# M1_75S2.net
KiCad netlist of a schematic drawn in Altium Designer
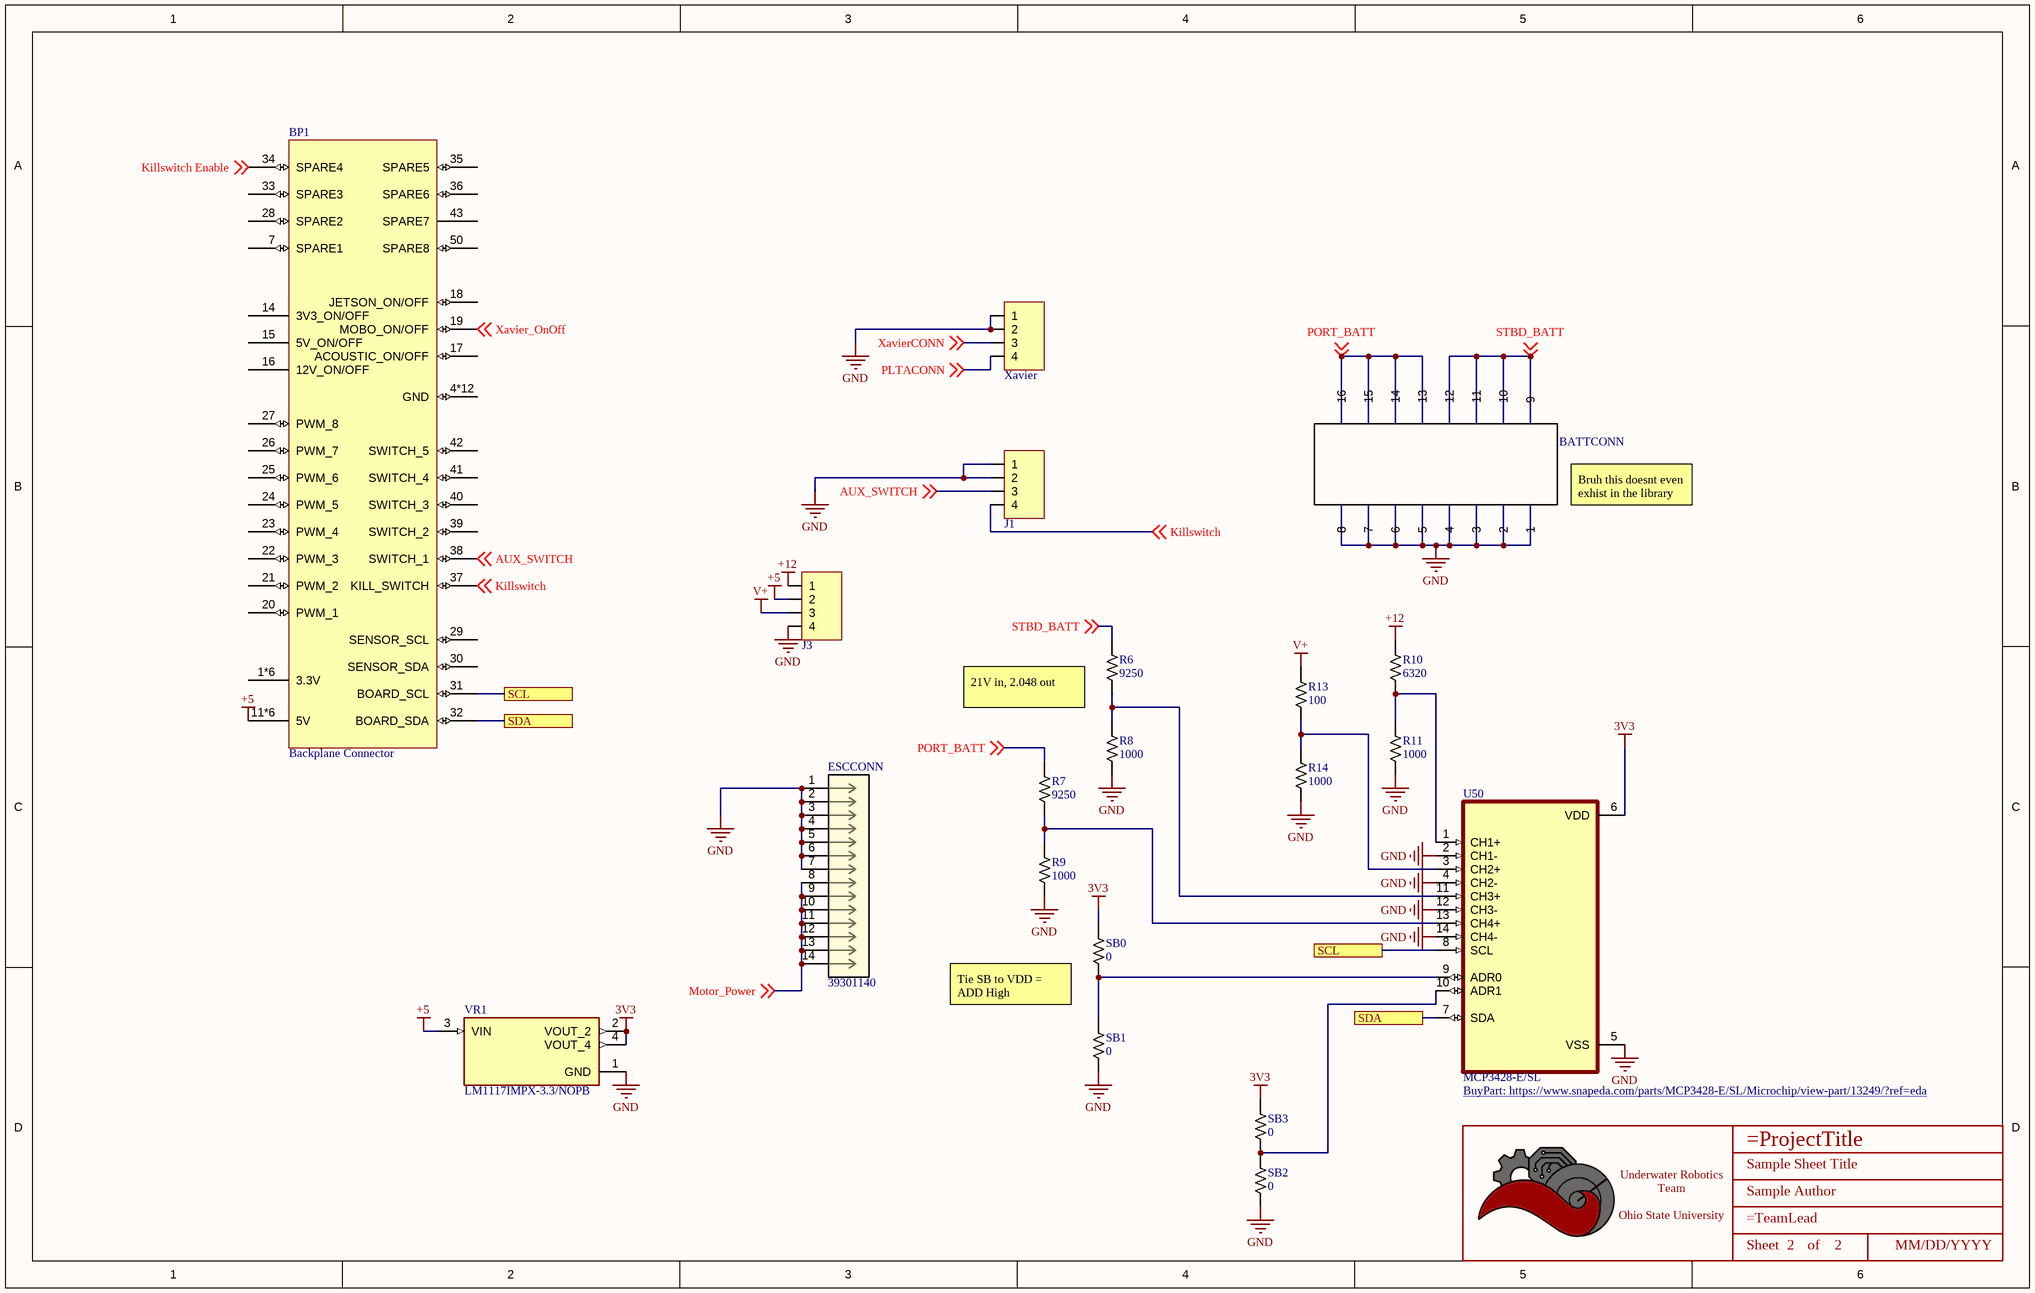
[diagram p0: M1_75S2.SchDoc]

(export (version "E")
  (design (tool "Eeschema 10.0.6"))
  (components
    (comp (ref "BATTCONN")
      (value "BatteryConnector")
      (footprint "CONN_MOLEX_MINIFIT JR_16 POS_R/A - duplicate")
      (libsource (lib "Connectors") (part "BatteryConnector"))
    )
    (comp (ref "BP1")
      (value "Backplane Connector")
      (footprint "BACKPLANE_EDGE_CONN")
      (description "Titan Backplane Edge Connector")
      (libsource (lib "Connectors") (part "BACKPLANE_EDGE_CONN"))
    )
    (comp (ref "ESCCONN")
      (value "39301140")
      (footprint "CON_39301140")
      (description "No Description Available")
      (fields (field (name "COPYRIGHT") "Copyright (C) 2022 Ultra Librarian. All rights reserved."))
      (libsource (lib "39301140") (part "39301140"))
    )
    (comp (ref "J1")
      (value "4 POS R/A")
      (footprint "CONN_MOLEX_MINIFIT JR_4 POS_R/A")
      (description "Molex Minifit Jr. 5569 \r\n4 Pos R/A Natural")
      (fields (field (name "MANUFACTURER") "Molex") (field (name "CREATED BY") "Flip B"))
      (libsource (lib "Connectors") (part "CONN_MOLEX_MINIFIT JR_4POS_R/A"))
    )
    (comp (ref "J3")
      (value "4 POS R/A")
      (footprint "CONN_MOLEX_MINIFIT JR_4 POS_R/A")
      (description "Molex Minifit Jr. 5569 \r\n4 Pos R/A Natural")
      (fields (field (name "MANUFACTURER") "Molex") (field (name "CREATED BY") "Flip B"))
      (libsource (lib "Connectors") (part "CONN_MOLEX_MINIFIT JR_4POS_R/A"))
    )
    (comp (ref "R6")
      (value "100 Ohm 5% 1/8W")
      (footprint "RESISTOR_0603")
      (description "RES 100 OHM 5% 1/8W 0603")
      (fields
        (field (name "TOLERANCE") "+/- 5%")
        (field (name "VALUE  (OHMS)") "9250")
        (field (name "MADE BY") "Flip B")
      )
      (libsource (lib "Resistors") (part "RESISTOR_100_0603"))
    )
    (comp (ref "R7")
      (value "100 Ohm 5% 1/8W")
      (footprint "RESISTOR_0603")
      (description "RES 100 OHM 5% 1/8W 0603")
      (fields
        (field (name "TOLERANCE") "+/- 5%")
        (field (name "VALUE  (OHMS)") "9250")
        (field (name "MADE BY") "Flip B")
      )
      (libsource (lib "Resistors") (part "RESISTOR_100_0603"))
    )
    (comp (ref "R8")
      (value "100 Ohm 5% 1/8W")
      (footprint "RESISTOR_0603")
      (description "RES 100 OHM 5% 1/8W 0603")
      (fields
        (field (name "TOLERANCE") "+/- 5%")
        (field (name "VALUE  (OHMS)") "1000")
        (field (name "MADE BY") "Flip B")
      )
      (libsource (lib "Resistors") (part "RESISTOR_100_0603"))
    )
    (comp (ref "R9")
      (value "100 Ohm 5% 1/8W")
      (footprint "RESISTOR_0603")
      (description "RES 100 OHM 5% 1/8W 0603")
      (fields
        (field (name "TOLERANCE") "+/- 5%")
        (field (name "VALUE  (OHMS)") "1000")
        (field (name "MADE BY") "Flip B")
      )
      (libsource (lib "Resistors") (part "RESISTOR_100_0603"))
    )
    (comp (ref "R10")
      (value "100 Ohm 5% 1/8W")
      (footprint "RESISTOR_0603")
      (description "RES 100 OHM 5% 1/8W 0603")
      (fields
        (field (name "TOLERANCE") "+/- 5%")
        (field (name "VALUE  (OHMS)") "6320")
        (field (name "MADE BY") "Flip B")
      )
      (libsource (lib "Resistors") (part "RESISTOR_100_0603"))
    )
    (comp (ref "R11")
      (value "100 Ohm 5% 1/8W")
      (footprint "RESISTOR_0603")
      (description "RES 100 OHM 5% 1/8W 0603")
      (fields
        (field (name "TOLERANCE") "+/- 5%")
        (field (name "VALUE  (OHMS)") "1000")
        (field (name "MADE BY") "Flip B")
      )
      (libsource (lib "Resistors") (part "RESISTOR_100_0603"))
    )
    (comp (ref "R13")
      (value "100 Ohm 5% 1/8W")
      (footprint "RESISTOR_0603")
      (description "RES 100 OHM 5% 1/8W 0603")
      (fields
        (field (name "TOLERANCE") "+/- 5%")
        (field (name "VALUE  (OHMS)") "100")
        (field (name "MADE BY") "Flip B")
      )
      (libsource (lib "Resistors") (part "RESISTOR_100_0603"))
    )
    (comp (ref "R14")
      (value "100 Ohm 5% 1/8W")
      (footprint "RESISTOR_0603")
      (description "RES 100 OHM 5% 1/8W 0603")
      (fields
        (field (name "TOLERANCE") "+/- 5%")
        (field (name "VALUE  (OHMS)") "1000")
        (field (name "MADE BY") "Flip B")
      )
      (libsource (lib "Resistors") (part "RESISTOR_100_0603"))
    )
    (comp (ref "SB0")
      (value "0 Ohm Jumper No Fit")
      (footprint "RESISTOR_0603")
      (description "0 Ohm Jumper No Fit for Solder Bridge")
      (fields (field (name "VALUE  (OHMS)") "0") (field (name "MADE BY") "Robert Pafford"))
      (libsource (lib "Resistors") (part "JUMPER_0_0603"))
    )
    (comp (ref "SB1")
      (value "0 Ohm Jumper No Fit")
      (footprint "RESISTOR_0603")
      (description "0 Ohm Jumper No Fit for Solder Bridge")
      (fields (field (name "VALUE  (OHMS)") "0") (field (name "MADE BY") "Robert Pafford"))
      (libsource (lib "Resistors") (part "JUMPER_0_0603"))
    )
    (comp (ref "SB2")
      (value "0 Ohm Jumper No Fit")
      (footprint "RESISTOR_0603")
      (description "0 Ohm Jumper No Fit for Solder Bridge")
      (fields (field (name "VALUE  (OHMS)") "0") (field (name "MADE BY") "Robert Pafford"))
      (libsource (lib "Resistors") (part "JUMPER_0_0603"))
    )
    (comp (ref "SB3")
      (value "0 Ohm Jumper No Fit")
      (footprint "RESISTOR_0603")
      (description "0 Ohm Jumper No Fit for Solder Bridge")
      (fields (field (name "VALUE  (OHMS)") "0") (field (name "MADE BY") "Robert Pafford"))
      (libsource (lib "Resistors") (part "JUMPER_0_0603"))
    )
    (comp (ref "U50")
      (value "MCP3428-E/SL")
      (footprint "SOIC127P600X175-14N")
      (description "16 Bit Analog to Digital Converter 4 Input 1 Sigma-Delta 14-SOIC")
      (fields
        (field (name "MF") "Microchip")
        (field (name "BUYPART") "https://www.snapeda.com/parts/MCP3428-E/SL/Microchip/view-part/13249/?ref=eda")
      )
      (libsource (lib "MCP3428-E_SL") (part "MCP3428-E/SL"))
    )
    (comp (ref "VR1")
      (value "LM1117IMPX-3.3/NOPB")
      (footprint "SOT-223-4")
      (description "800-mA 15-V linear voltage regulator 4-SOT-223 -40 to 125")
      (fields (field (name "MF") "Texas Instruments"))
      (libsource (lib "Integrated Circuits") (part "LM1117IMPX-3.3/NOPB"))
    )
    (comp (ref "Xavier")
      (value "4 POS R/A")
      (footprint "CONN_MOLEX_MINIFIT JR_4 POS_R/A")
      (description "Molex Minifit Jr. 5569 \r\n4 Pos R/A Natural")
      (fields (field (name "MANUFACTURER") "Molex") (field (name "CREATED BY") "Flip B"))
      (libsource (lib "Connectors") (part "CONN_MOLEX_MINIFIT JR_4POS_R/A"))
    )
  )
  (nets
    (net (code "1") (name "+5") (class "Default")
      (node (ref "BP1") (pin "11*6") (pinfunction "5V_11*6") (pintype "power_in"))
      (node (ref "J3") (pin "2") (pinfunction "2_2") (pintype "passive"))
      (node (ref "VR1") (pin "3") (pinfunction "VIN_3") (pintype "input"))
    )
    (net (code "2") (name "+12") (class "Default")
      (node (ref "J3") (pin "1") (pinfunction "1_1") (pintype "passive"))
      (node (ref "R10") (pin "1") (pinfunction "1_1") (pintype "passive"))
    )
    (net (code "3") (name "/SCL") (class "Default")
      (node (ref "BP1") (pin "31") (pinfunction "BOARD_SCL_31") (pintype "bidirectional"))
      (node (ref "U50") (pin "8") (pinfunction "SCL_8") (pintype "input"))
    )
    (net (code "4") (name "/SDA") (class "Default")
      (node (ref "BP1") (pin "32") (pinfunction "BOARD_SDA_32") (pintype "bidirectional"))
      (node (ref "U50") (pin "7") (pinfunction "SDA_7") (pintype "bidirectional"))
    )
    (net (code "5") (name "3V3") (class "Default")
      (node (ref "SB0") (pin "1") (pinfunction "1_1") (pintype "passive"))
      (node (ref "SB3") (pin "1") (pinfunction "1_1") (pintype "passive"))
      (node (ref "U50") (pin "6") (pinfunction "VDD_6") (pintype "power_in"))
      (node (ref "VR1") (pin "2") (pinfunction "VOUT_2_2") (pintype "output"))
      (node (ref "VR1") (pin "4") (pinfunction "VOUT_4_4") (pintype "output"))
    )
    (net (code "6") (name "AUX_SWITCH") (class "Default")
      (node (ref "BP1") (pin "38") (pinfunction "SWITCH_1_38") (pintype "bidirectional"))
      (node (ref "J1") (pin "3") (pinfunction "3_3") (pintype "passive"))
    )
    (net (code "7") (name "GND") (class "Default")
      (node (ref "BATTCONN") (pin "1") (pinfunction "1_1") (pintype "passive"))
      (node (ref "BATTCONN") (pin "2") (pinfunction "2_2") (pintype "passive"))
      (node (ref "BATTCONN") (pin "3") (pinfunction "3_3") (pintype "passive"))
      (node (ref "BATTCONN") (pin "4") (pinfunction "4_4") (pintype "passive"))
      (node (ref "BATTCONN") (pin "5") (pinfunction "5_5") (pintype "passive"))
      (node (ref "BATTCONN") (pin "6") (pinfunction "6_6") (pintype "passive"))
      (node (ref "BATTCONN") (pin "7") (pinfunction "7_7") (pintype "passive"))
      (node (ref "BATTCONN") (pin "8") (pinfunction "8_8") (pintype "passive"))
      (node (ref "ESCCONN") (pin "1") (pinfunction "1_1") (pintype "passive"))
      (node (ref "ESCCONN") (pin "2") (pinfunction "2_2") (pintype "passive"))
      (node (ref "ESCCONN") (pin "3") (pinfunction "3_3") (pintype "passive"))
      (node (ref "ESCCONN") (pin "4") (pinfunction "4_4") (pintype "passive"))
      (node (ref "ESCCONN") (pin "5") (pinfunction "5_5") (pintype "passive"))
      (node (ref "ESCCONN") (pin "6") (pinfunction "6_6") (pintype "passive"))
      (node (ref "ESCCONN") (pin "7") (pinfunction "7_7") (pintype "passive"))
      (node (ref "J1") (pin "1") (pinfunction "1_1") (pintype "passive"))
      (node (ref "J1") (pin "2") (pinfunction "2_2") (pintype "passive"))
      (node (ref "J3") (pin "4") (pinfunction "4_4") (pintype "passive"))
      (node (ref "R11") (pin "2") (pinfunction "2_2") (pintype "passive"))
      (node (ref "R14") (pin "2") (pinfunction "2_2") (pintype "passive"))
      (node (ref "R8") (pin "2") (pinfunction "2_2") (pintype "passive"))
      (node (ref "R9") (pin "2") (pinfunction "2_2") (pintype "passive"))
      (node (ref "SB1") (pin "2") (pinfunction "2_2") (pintype "passive"))
      (node (ref "SB2") (pin "2") (pinfunction "2_2") (pintype "passive"))
      (node (ref "U50") (pin "12") (pinfunction "CH3-_12") (pintype "input"))
      (node (ref "U50") (pin "14") (pinfunction "CH4-_14") (pintype "input"))
      (node (ref "U50") (pin "2") (pinfunction "CH1-_2") (pintype "input"))
      (node (ref "U50") (pin "4") (pinfunction "CH2-_4") (pintype "input"))
      (node (ref "U50") (pin "5") (pinfunction "VSS_5") (pintype "power_in"))
      (node (ref "VR1") (pin "1") (pinfunction "GND_1") (pintype "power_in"))
      (node (ref "Xavier") (pin "1") (pinfunction "1_1") (pintype "passive"))
      (node (ref "Xavier") (pin "2") (pinfunction "2_2") (pintype "passive"))
    )
    (net (code "8") (name "Killswitch") (class "Default")
      (node (ref "BP1") (pin "37") (pinfunction "KILL_SWITCH_37") (pintype "bidirectional"))
      (node (ref "J1") (pin "4") (pinfunction "4_4") (pintype "passive"))
    )
    (net (code "9") (name "Killswitch Enable") (class "Default")
      (node (ref "BP1") (pin "34") (pinfunction "SPARE4_34") (pintype "bidirectional"))
    )
    (net (code "10") (name "Motor_Power") (class "Default")
      (node (ref "ESCCONN") (pin "10") (pinfunction "10_10") (pintype "passive"))
      (node (ref "ESCCONN") (pin "11") (pinfunction "11_11") (pintype "passive"))
      (node (ref "ESCCONN") (pin "12") (pinfunction "12_12") (pintype "passive"))
      (node (ref "ESCCONN") (pin "13") (pinfunction "13_13") (pintype "passive"))
      (node (ref "ESCCONN") (pin "14") (pinfunction "14_14") (pintype "passive"))
      (node (ref "ESCCONN") (pin "8") (pinfunction "8_8") (pintype "passive"))
      (node (ref "ESCCONN") (pin "9") (pinfunction "9_9") (pintype "passive"))
    )
    (net (code "11") (name "Net-(U50-ADR0)") (class "Default")
      (node (ref "SB0") (pin "2") (pinfunction "2_2") (pintype "passive"))
      (node (ref "SB1") (pin "1") (pinfunction "1_1") (pintype "passive"))
      (node (ref "U50") (pin "9") (pinfunction "ADR0_9") (pintype "bidirectional"))
    )
    (net (code "12") (name "Net-(U50-ADR1)") (class "Default")
      (node (ref "SB2") (pin "1") (pinfunction "1_1") (pintype "passive"))
      (node (ref "SB3") (pin "2") (pinfunction "2_2") (pintype "passive"))
      (node (ref "U50") (pin "10") (pinfunction "ADR1_10") (pintype "bidirectional"))
    )
    (net (code "13") (name "Net-(U50-CH1+)") (class "Default")
      (node (ref "R10") (pin "2") (pinfunction "2_2") (pintype "passive"))
      (node (ref "R11") (pin "1") (pinfunction "1_1") (pintype "passive"))
      (node (ref "U50") (pin "1") (pinfunction "CH1+_1") (pintype "input"))
    )
    (net (code "14") (name "Net-(U50-CH2+)") (class "Default")
      (node (ref "R13") (pin "2") (pinfunction "2_2") (pintype "passive"))
      (node (ref "R14") (pin "1") (pinfunction "1_1") (pintype "passive"))
      (node (ref "U50") (pin "3") (pinfunction "CH2+_3") (pintype "input"))
    )
    (net (code "15") (name "Net-(U50-CH3+)") (class "Default")
      (node (ref "R6") (pin "2") (pinfunction "2_2") (pintype "passive"))
      (node (ref "R8") (pin "1") (pinfunction "1_1") (pintype "passive"))
      (node (ref "U50") (pin "11") (pinfunction "CH3+_11") (pintype "input"))
    )
    (net (code "16") (name "Net-(U50-CH4+)") (class "Default")
      (node (ref "R7") (pin "2") (pinfunction "2_2") (pintype "passive"))
      (node (ref "R9") (pin "1") (pinfunction "1_1") (pintype "passive"))
      (node (ref "U50") (pin "13") (pinfunction "CH4+_13") (pintype "input"))
    )
    (net (code "17") (name "PLTACONN") (class "Default")
      (node (ref "Xavier") (pin "4") (pinfunction "4_4") (pintype "passive"))
    )
    (net (code "18") (name "PORT_BATT") (class "Default")
      (node (ref "BATTCONN") (pin "13") (pinfunction "13_13") (pintype "passive"))
      (node (ref "BATTCONN") (pin "14") (pinfunction "14_14") (pintype "passive"))
      (node (ref "BATTCONN") (pin "15") (pinfunction "15_15") (pintype "passive"))
      (node (ref "BATTCONN") (pin "16") (pinfunction "16_16") (pintype "passive"))
      (node (ref "R7") (pin "1") (pinfunction "1_1") (pintype "passive"))
    )
    (net (code "19") (name "STBD_BATT") (class "Default")
      (node (ref "BATTCONN") (pin "10") (pinfunction "10_10") (pintype "passive"))
      (node (ref "BATTCONN") (pin "11") (pinfunction "11_11") (pintype "passive"))
      (node (ref "BATTCONN") (pin "12") (pinfunction "12_12") (pintype "passive"))
      (node (ref "BATTCONN") (pin "9") (pinfunction "9_9") (pintype "passive"))
      (node (ref "R6") (pin "1") (pinfunction "1_1") (pintype "passive"))
    )
    (net (code "20") (name "V+") (class "Default")
      (node (ref "J3") (pin "3") (pinfunction "3_3") (pintype "passive"))
      (node (ref "R13") (pin "1") (pinfunction "1_1") (pintype "passive"))
    )
    (net (code "21") (name "XavierCONN") (class "Default")
      (node (ref "Xavier") (pin "3") (pinfunction "3_3") (pintype "passive"))
    )
    (net (code "22") (name "Xavier_OnOff") (class "Default")
      (node (ref "BP1") (pin "19") (pinfunction "MOBO_ON/OFF_19") (pintype "bidirectional"))
    )
    (net (code "23") (name "unconnected-(BP1-3.3V-Pad1*6)") (class "Default")
      (node (ref "BP1") (pin "1*6") (pinfunction "3.3V_1*6") (pintype "power_in"))
    )
    (net (code "24") (name "unconnected-(BP1-3V3_ON{slash}OFF-Pad14)") (class "Default")
      (node (ref "BP1") (pin "14") (pinfunction "3V3_ON/OFF_14") (pintype "power_in"))
    )
    (net (code "25") (name "unconnected-(BP1-5V_ON{slash}OFF-Pad15)") (class "Default")
      (node (ref "BP1") (pin "15") (pinfunction "5V_ON/OFF_15") (pintype "power_in"))
    )
    (net (code "26") (name "unconnected-(BP1-12V_ON{slash}OFF-Pad16)") (class "Default")
      (node (ref "BP1") (pin "16") (pinfunction "12V_ON/OFF_16") (pintype "power_in"))
    )
    (net (code "27") (name "unconnected-(BP1-ACOUSTIC_ON{slash}OFF-Pad17)") (class "Default")
      (node (ref "BP1") (pin "17") (pinfunction "ACOUSTIC_ON/OFF_17") (pintype "bidirectional"))
    )
    (net (code "28") (name "unconnected-(BP1-GND-Pad4*12)") (class "Default")
      (node (ref "BP1") (pin "4*12") (pinfunction "GND_4*12") (pintype "bidirectional"))
    )
    (net (code "29") (name "unconnected-(BP1-JETSON_ON{slash}OFF-Pad18)") (class "Default")
      (node (ref "BP1") (pin "18") (pinfunction "JETSON_ON/OFF_18") (pintype "bidirectional"))
    )
    (net (code "30") (name "unconnected-(BP1-PWM_1-Pad20)") (class "Default")
      (node (ref "BP1") (pin "20") (pinfunction "PWM_1_20") (pintype "bidirectional"))
    )
    (net (code "31") (name "unconnected-(BP1-PWM_2-Pad21)") (class "Default")
      (node (ref "BP1") (pin "21") (pinfunction "PWM_2_21") (pintype "bidirectional"))
    )
    (net (code "32") (name "unconnected-(BP1-PWM_3-Pad22)") (class "Default")
      (node (ref "BP1") (pin "22") (pinfunction "PWM_3_22") (pintype "bidirectional"))
    )
    (net (code "33") (name "unconnected-(BP1-PWM_4-Pad23)") (class "Default")
      (node (ref "BP1") (pin "23") (pinfunction "PWM_4_23") (pintype "bidirectional"))
    )
    (net (code "34") (name "unconnected-(BP1-PWM_5-Pad24)") (class "Default")
      (node (ref "BP1") (pin "24") (pinfunction "PWM_5_24") (pintype "bidirectional"))
    )
    (net (code "35") (name "unconnected-(BP1-PWM_6-Pad25)") (class "Default")
      (node (ref "BP1") (pin "25") (pinfunction "PWM_6_25") (pintype "bidirectional"))
    )
    (net (code "36") (name "unconnected-(BP1-PWM_7-Pad26)") (class "Default")
      (node (ref "BP1") (pin "26") (pinfunction "PWM_7_26") (pintype "bidirectional"))
    )
    (net (code "37") (name "unconnected-(BP1-PWM_8-Pad27)") (class "Default")
      (node (ref "BP1") (pin "27") (pinfunction "PWM_8_27") (pintype "bidirectional"))
    )
    (net (code "38") (name "unconnected-(BP1-SENSOR_SCL-Pad29)") (class "Default")
      (node (ref "BP1") (pin "29") (pinfunction "SENSOR_SCL_29") (pintype "bidirectional"))
    )
    (net (code "39") (name "unconnected-(BP1-SENSOR_SDA-Pad30)") (class "Default")
      (node (ref "BP1") (pin "30") (pinfunction "SENSOR_SDA_30") (pintype "bidirectional"))
    )
    (net (code "40") (name "unconnected-(BP1-SPARE1-Pad7)") (class "Default")
      (node (ref "BP1") (pin "7") (pinfunction "SPARE1_7") (pintype "bidirectional"))
    )
    (net (code "41") (name "unconnected-(BP1-SPARE2-Pad28)") (class "Default")
      (node (ref "BP1") (pin "28") (pinfunction "SPARE2_28") (pintype "bidirectional"))
    )
    (net (code "42") (name "unconnected-(BP1-SPARE3-Pad33)") (class "Default")
      (node (ref "BP1") (pin "33") (pinfunction "SPARE3_33") (pintype "bidirectional"))
    )
    (net (code "43") (name "unconnected-(BP1-SPARE5-Pad35)") (class "Default")
      (node (ref "BP1") (pin "35") (pinfunction "SPARE5_35") (pintype "bidirectional"))
    )
    (net (code "44") (name "unconnected-(BP1-SPARE6-Pad36)") (class "Default")
      (node (ref "BP1") (pin "36") (pinfunction "SPARE6_36") (pintype "bidirectional"))
    )
    (net (code "45") (name "unconnected-(BP1-SPARE7-Pad43)") (class "Default")
      (node (ref "BP1") (pin "43") (pinfunction "SPARE7_43") (pintype "power_in"))
    )
    (net (code "46") (name "unconnected-(BP1-SPARE8-Pad50)") (class "Default")
      (node (ref "BP1") (pin "50") (pinfunction "SPARE8_50") (pintype "bidirectional"))
    )
    (net (code "47") (name "unconnected-(BP1-SWITCH_2-Pad39)") (class "Default")
      (node (ref "BP1") (pin "39") (pinfunction "SWITCH_2_39") (pintype "bidirectional"))
    )
    (net (code "48") (name "unconnected-(BP1-SWITCH_3-Pad40)") (class "Default")
      (node (ref "BP1") (pin "40") (pinfunction "SWITCH_3_40") (pintype "bidirectional"))
    )
    (net (code "49") (name "unconnected-(BP1-SWITCH_4-Pad41)") (class "Default")
      (node (ref "BP1") (pin "41") (pinfunction "SWITCH_4_41") (pintype "bidirectional"))
    )
    (net (code "50") (name "unconnected-(BP1-SWITCH_5-Pad42)") (class "Default")
      (node (ref "BP1") (pin "42") (pinfunction "SWITCH_5_42") (pintype "bidirectional"))
    )
  )
)
